# ProPrj_ExtModule-003_2025-06-06.net
KiCad netlist of a schematic drawn in EasyEDA Pro
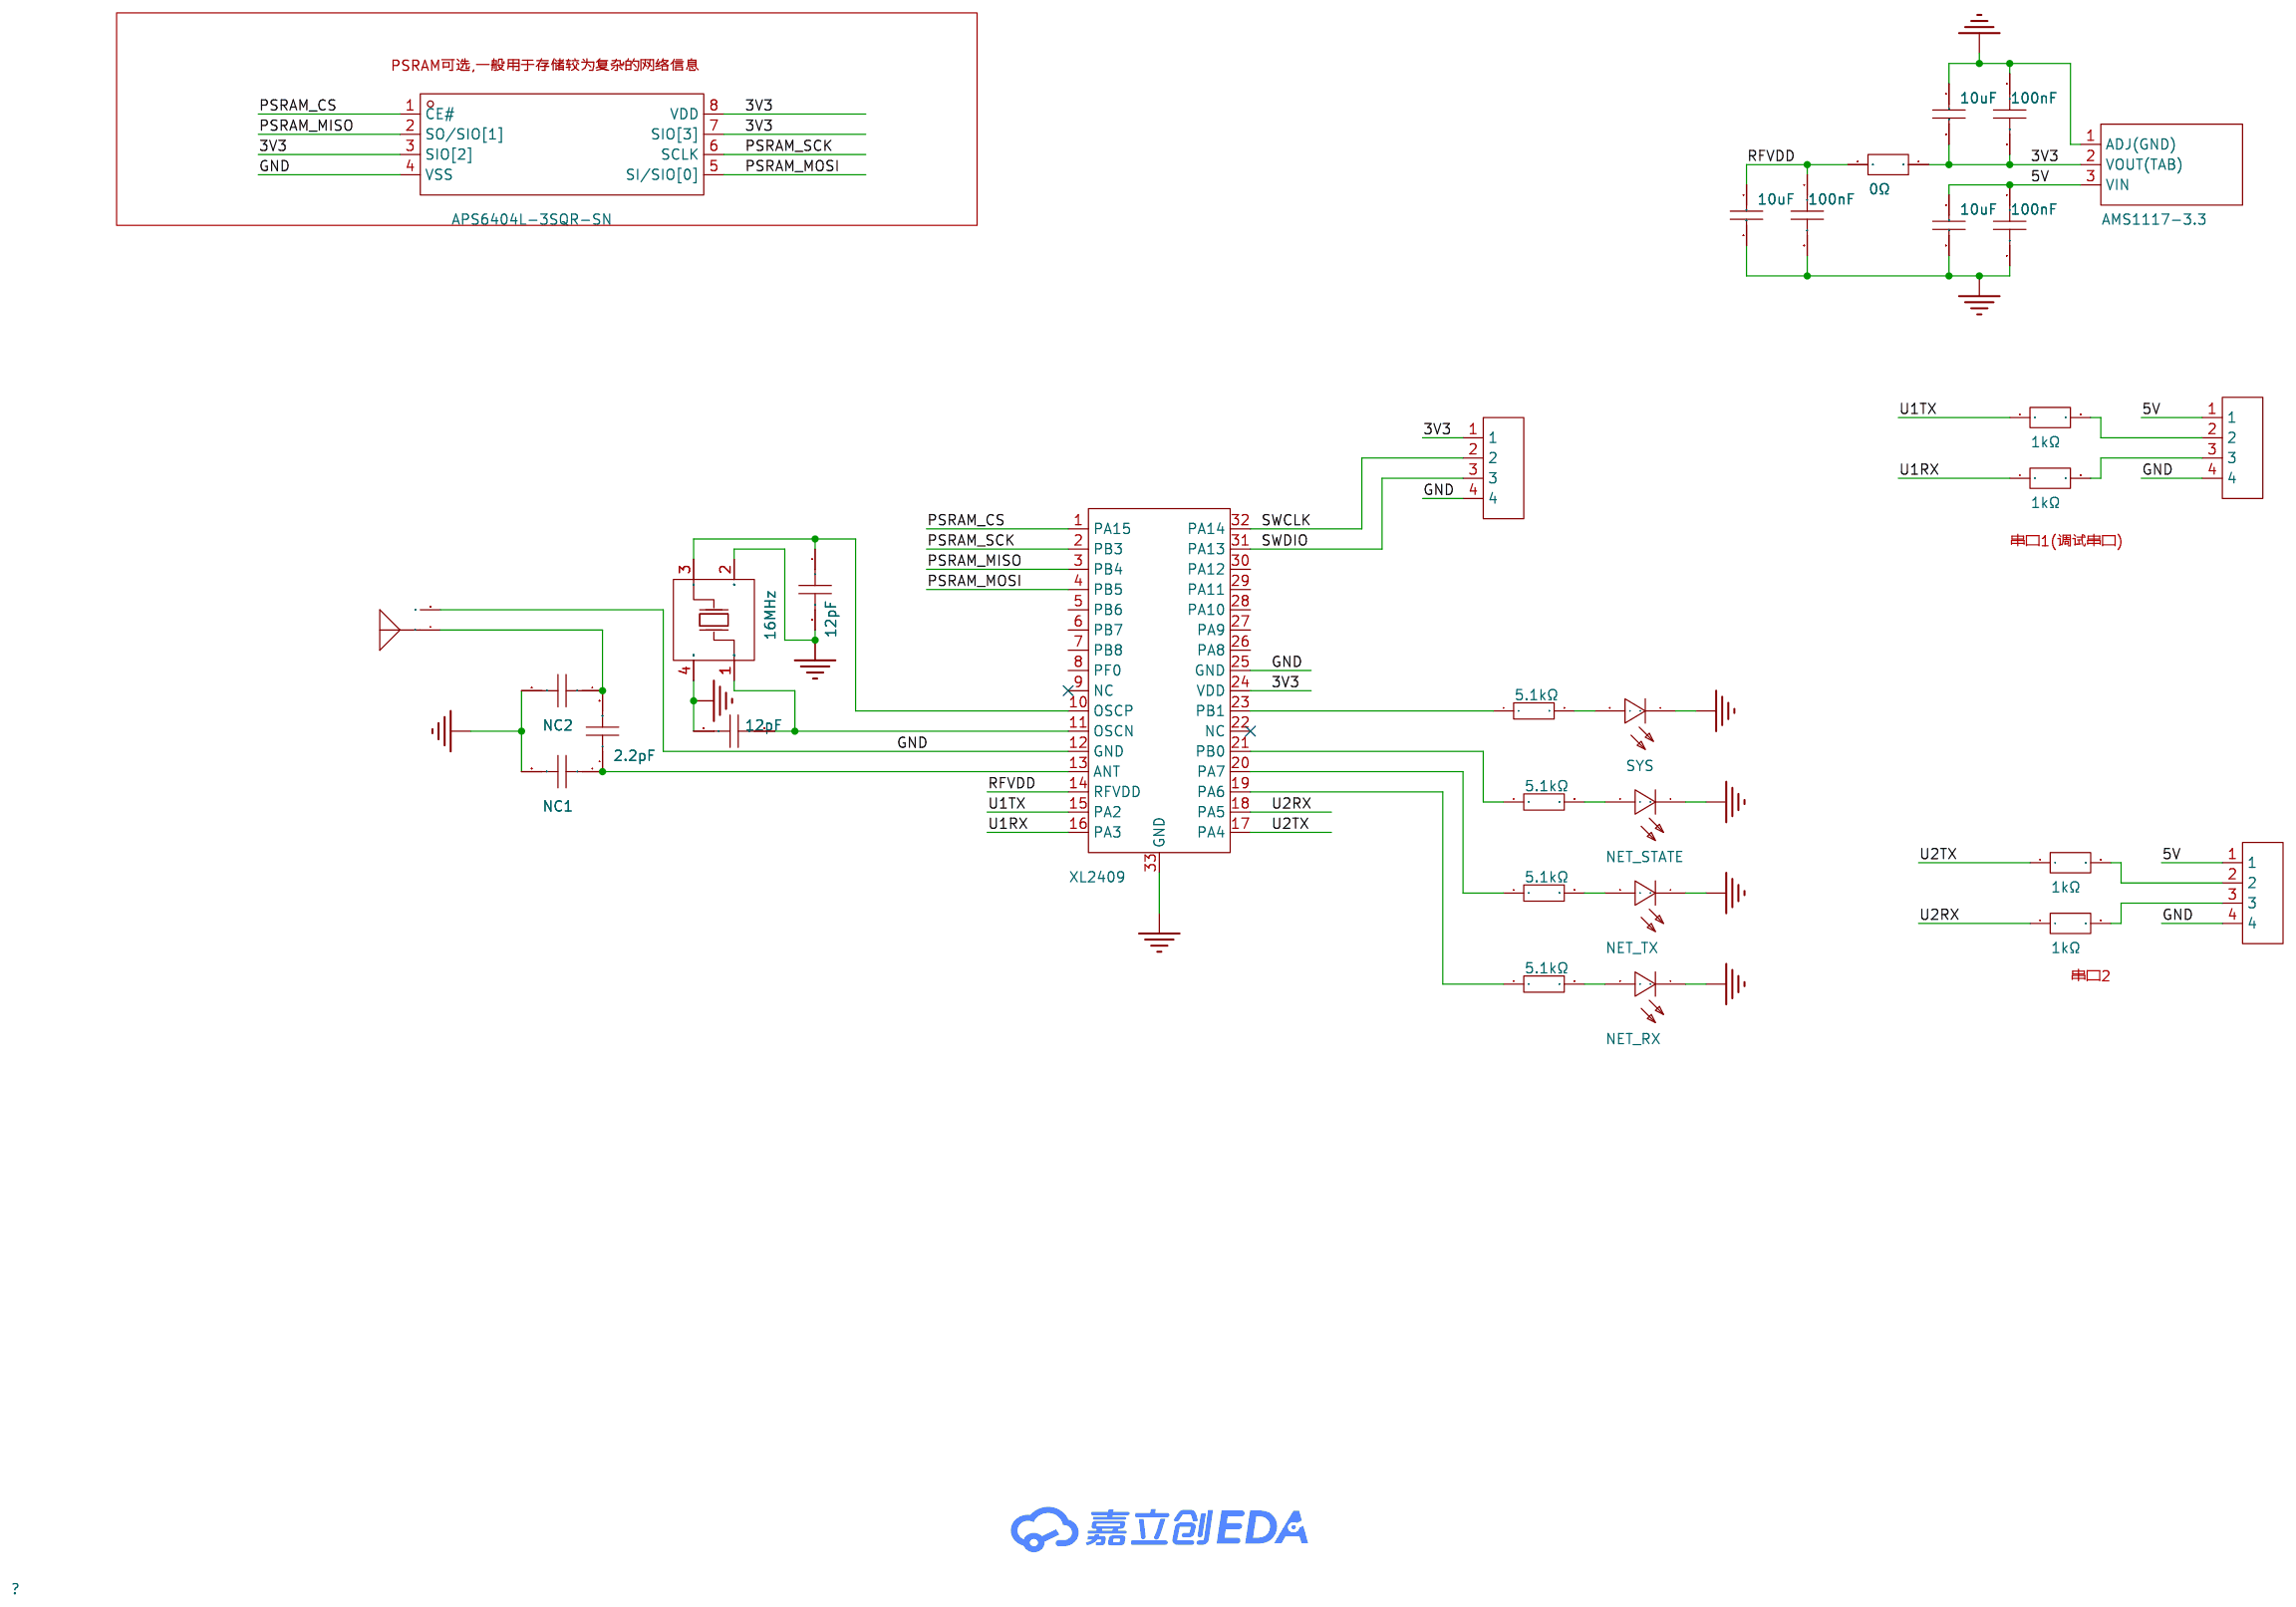
[diagram p0: schematic sheet]

(export (version "E")
  (design (tool "Eeschema 10.0.6"))
  (components
    (comp (ref "C3")
      (value "100nF")
      (footprint "easyedapro:C0402")
      (description "容值:100nF;精度:±10%;额定电压:16V;材质(温度系数):X7R;")
      (fields
        (field (name "Manufacturer Part") "CC0402KRX7R7BB104")
        (field (name "Manufacturer") "YAGEO(国巨)")
      )
      (libsource (lib "easyedapro") (part "CC0402KRX7R7BB104"))
    )
    (comp (ref "C4")
      (value "10uF")
      (footprint "easyedapro:C0402")
      (description "容值:10uF;精度:±20%;额定电压:6.3V;材质(温度系数):X5R;")
      (fields
        (field (name "Manufacturer Part") "CL05A106MQ5NUNC")
        (field (name "Manufacturer") "SAMSUNG(三星)")
      )
      (libsource (lib "easyedapro") (part "CL05A106MQ5NUNC"))
    )
    (comp (ref "C5")
      (value "10uF")
      (footprint "easyedapro:C0402")
      (description "容值:10uF;精度:±20%;额定电压:6.3V;材质(温度系数):X5R;")
      (fields
        (field (name "Manufacturer Part") "CL05A106MQ5NUNC")
        (field (name "Manufacturer") "SAMSUNG(三星)")
      )
      (libsource (lib "easyedapro") (part "CL05A106MQ5NUNC"))
    )
    (comp (ref "C6")
      (value "100nF")
      (footprint "easyedapro:C0402")
      (description "容值:100nF;精度:±10%;额定电压:16V;材质(温度系数):X7R;")
      (fields
        (field (name "Manufacturer Part") "CC0402KRX7R7BB104")
        (field (name "Manufacturer") "YAGEO(国巨)")
      )
      (libsource (lib "easyedapro") (part "CC0402KRX7R7BB104"))
    )
    (comp (ref "C7")
      (value "10uF")
      (footprint "easyedapro:C0402")
      (description "容值:10uF;精度:±20%;额定电压:6.3V;材质(温度系数):X5R;")
      (fields
        (field (name "Manufacturer Part") "CL05A106MQ5NUNC")
        (field (name "Manufacturer") "SAMSUNG(三星)")
      )
      (libsource (lib "easyedapro") (part "CL05A106MQ5NUNC"))
    )
    (comp (ref "C8")
      (value "100nF")
      (footprint "easyedapro:C0402")
      (description "容值:100nF;精度:±10%;额定电压:16V;材质(温度系数):X7R;")
      (fields
        (field (name "Manufacturer Part") "CC0402KRX7R7BB104")
        (field (name "Manufacturer") "YAGEO(国巨)")
      )
      (libsource (lib "easyedapro") (part "CC0402KRX7R7BB104"))
    )
    (comp (ref "C9")
      (value "2.2pF")
      (footprint "easyedapro:C0402")
      (description "容值:2.2pF;额定电压:50V;材质(温度系数):NP0;")
      (fields
        (field (name "Manufacturer Part") "CC0402BRNPO9BN2R2")
        (field (name "Manufacturer") "YAGEO(国巨)")
      )
      (libsource (lib "easyedapro") (part "CC0402BRNPO9BN2R2"))
    )
    (comp (ref "C10")
      (value "12pF")
      (footprint "easyedapro:C0402")
      (description "容值:12pF;精度:±1%;额定电压:50V;材质(温度系数):NP0;")
      (fields
        (field (name "Manufacturer Part") "CC0402FRNPO9BN120")
        (field (name "Manufacturer") "YAGEO(国巨)")
      )
      (libsource (lib "easyedapro") (part "CC0402FRNPO9BN120"))
    )
    (comp (ref "C11")
      (value "12pF")
      (footprint "easyedapro:C0402")
      (description "容值:12pF;精度:±1%;额定电压:50V;材质(温度系数):NP0;")
      (fields
        (field (name "Manufacturer Part") "CC0402FRNPO9BN120")
        (field (name "Manufacturer") "YAGEO(国巨)")
      )
      (libsource (lib "easyedapro") (part "CC0402FRNPO9BN120"))
    )
    (comp (ref "H1")
      (value "PZ254R-11-04P")
      (footprint "easyedapro:HDR-TH_4P-P2.54-H-M-W10.4")
      (fields (field (name "Manufacturer") "XFCN(兴飞)"))
      (libsource (lib "easyedapro") (part "PZ254R-11-04P"))
    )
    (comp (ref "H2")
      (value "PZ254R-11-04P")
      (footprint "easyedapro:HDR-TH_4P-P2.54-H-M-W10.4")
      (fields (field (name "Manufacturer") "XFCN(兴飞)"))
      (libsource (lib "easyedapro") (part "PZ254R-11-04P"))
    )
    (comp (ref "H3")
      (value "PZ254R-11-04P")
      (footprint "easyedapro:HDR-TH_4P-P2.54-H-M-W10.4")
      (fields (field (name "Manufacturer") "XFCN(兴飞)"))
      (libsource (lib "easyedapro") (part "PZ254R-11-04P"))
    )
    (comp (ref "L1")
      (value "KH-3216-A27")
      (footprint "easyedapro:ANT-SMD_L3.2-W1.6")
      (fields (field (name "Manufacturer") "kinghelm(金航标)"))
      (libsource (lib "easyedapro") (part "KH-3216-A27"))
    )
    (comp (ref "LED2")
      (value "SYS")
      (footprint "easyedapro:LED0603-RD_RED")
      (fields (field (name "Manufacturer Part") "NCD0603R1") (field (name "Manufacturer") "国星光电"))
      (libsource (lib "easyedapro") (part "FC-DA1608HRK-620D"))
    )
    (comp (ref "LED3")
      (value "NET_STATE")
      (footprint "easyedapro:LED0603-RD_RED")
      (fields (field (name "Manufacturer Part") "NCD0603R1") (field (name "Manufacturer") "国星光电"))
      (libsource (lib "easyedapro") (part "FC-DA1608HRK-620D"))
    )
    (comp (ref "LED4")
      (value "NET_TX")
      (footprint "easyedapro:LED0603-RD_RED")
      (fields (field (name "Manufacturer Part") "NCD0603R1") (field (name "Manufacturer") "国星光电"))
      (libsource (lib "easyedapro") (part "FC-DA1608HRK-620D"))
    )
    (comp (ref "LED5")
      (value "NET_RX")
      (footprint "easyedapro:LED0603-RD_RED")
      (fields (field (name "Manufacturer Part") "NCD0603R1") (field (name "Manufacturer") "国星光电"))
      (libsource (lib "easyedapro") (part "FC-DA1608HRK-620D"))
    )
    (comp (ref "NC1")
      (value "9pF")
      (footprint "easyedapro:C0402")
      (description "容值:9pF;额定电压:50V;材质(温度系数):NP0;")
      (fields
        (field (name "Manufacturer Part") "CC0402CRNPO9BN9R0")
        (field (name "Manufacturer") "YAGEO(国巨)")
      )
      (libsource (lib "easyedapro") (part "CC0402CRNPO9BN9R0"))
    )
    (comp (ref "NC2")
      (value "9pF")
      (footprint "easyedapro:C0402")
      (description "容值:9pF;额定电压:50V;材质(温度系数):NP0;")
      (fields
        (field (name "Manufacturer Part") "CC0402CRNPO9BN9R0")
        (field (name "Manufacturer") "YAGEO(国巨)")
      )
      (libsource (lib "easyedapro") (part "CC0402CRNPO9BN9R0"))
    )
    (comp (ref "R1")
      (value "0Ω")
      (footprint "easyedapro:R0402")
      (description "电阻类型:厚膜电阻;阻值:0Ω;精度:±5%;功率:62.5mW;最大工作电压:50V;")
      (fields (field (name "Manufacturer Part") "FRC0402P000 TS") (field (name "Manufacturer") "FOJAN(富捷)"))
      (libsource (lib "easyedapro") (part "FRC0402P000 TS"))
    )
    (comp (ref "R18")
      (value "5.1kΩ")
      (footprint "easyedapro:R0402")
      (description "阻值:5.1kΩ;精度:±1%;功率:62.5mW;温度系数:±100ppm/°C;电阻类型:厚膜电阻;")
      (fields
        (field (name "Manufacturer Part") "0402WGF5101TCE")
        (field (name "Manufacturer") "UNI-ROYAL(厚声)")
      )
      (libsource (lib "easyedapro") (part "0402WGF5101TCE"))
    )
    (comp (ref "R19")
      (value "5.1kΩ")
      (footprint "easyedapro:R0402")
      (description "阻值:5.1kΩ;精度:±1%;功率:62.5mW;温度系数:±100ppm/°C;电阻类型:厚膜电阻;")
      (fields
        (field (name "Manufacturer Part") "0402WGF5101TCE")
        (field (name "Manufacturer") "UNI-ROYAL(厚声)")
      )
      (libsource (lib "easyedapro") (part "0402WGF5101TCE"))
    )
    (comp (ref "R20")
      (value "5.1kΩ")
      (footprint "easyedapro:R0402")
      (description "阻值:5.1kΩ;精度:±1%;功率:62.5mW;温度系数:±100ppm/°C;电阻类型:厚膜电阻;")
      (fields
        (field (name "Manufacturer Part") "0402WGF5101TCE")
        (field (name "Manufacturer") "UNI-ROYAL(厚声)")
      )
      (libsource (lib "easyedapro") (part "0402WGF5101TCE"))
    )
    (comp (ref "R21")
      (value "5.1kΩ")
      (footprint "easyedapro:R0402")
      (description "阻值:5.1kΩ;精度:±1%;功率:62.5mW;温度系数:±100ppm/°C;电阻类型:厚膜电阻;")
      (fields
        (field (name "Manufacturer Part") "0402WGF5101TCE")
        (field (name "Manufacturer") "UNI-ROYAL(厚声)")
      )
      (libsource (lib "easyedapro") (part "0402WGF5101TCE"))
    )
    (comp (ref "R22")
      (value "1kΩ")
      (footprint "easyedapro:R0402")
      (description "电阻类型:薄膜电阻;阻值:1kΩ;精度:±0.1%;功率:62.5mW;最大工作电压:50V;温度系数:±25ppm/°C;")
      (fields (field (name "Manufacturer Part") "RT0402BRD071KL") (field (name "Manufacturer") "YAGEO(国巨)"))
      (libsource (lib "easyedapro") (part "RT0402BRD071KL"))
    )
    (comp (ref "R23")
      (value "1kΩ")
      (footprint "easyedapro:R0402")
      (description "电阻类型:薄膜电阻;阻值:1kΩ;精度:±0.1%;功率:62.5mW;最大工作电压:50V;温度系数:±25ppm/°C;")
      (fields (field (name "Manufacturer Part") "RT0402BRD071KL") (field (name "Manufacturer") "YAGEO(国巨)"))
      (libsource (lib "easyedapro") (part "RT0402BRD071KL"))
    )
    (comp (ref "R24")
      (value "1kΩ")
      (footprint "easyedapro:R0402")
      (description "电阻类型:薄膜电阻;阻值:1kΩ;精度:±0.1%;功率:62.5mW;最大工作电压:50V;温度系数:±25ppm/°C;")
      (fields (field (name "Manufacturer Part") "RT0402BRD071KL") (field (name "Manufacturer") "YAGEO(国巨)"))
      (libsource (lib "easyedapro") (part "RT0402BRD071KL"))
    )
    (comp (ref "R25")
      (value "1kΩ")
      (footprint "easyedapro:R0402")
      (description "电阻类型:薄膜电阻;阻值:1kΩ;精度:±0.1%;功率:62.5mW;最大工作电压:50V;温度系数:±25ppm/°C;")
      (fields (field (name "Manufacturer Part") "RT0402BRD071KL") (field (name "Manufacturer") "YAGEO(国巨)"))
      (libsource (lib "easyedapro") (part "RT0402BRD071KL"))
    )
    (comp (ref "U1")
      (value "XL2409")
      (footprint "easyedapro:QFN-32_L4.0-W4.0-P0.40-BL-EP2.7-A")
      (libsource (lib "easyedapro") (part "XL2409"))
    )
    (comp (ref "U2")
      (value "AMS1117-3.3")
      (footprint "easyedapro:SOT-89_L4.5-W2.5-P1.50-LS4.2-BR")
      (description "输出类型:固定;工作电压:18V;输出电压:3.3V;输出电流:1A;电源纹波抑制比(PSRR):60dB@(120Hz);输出极性:正极;")
      (fields (field (name "Manufacturer") "UMW(友台半导体)"))
      (libsource (lib "easyedapro") (part "AMS1117-3.3_C347256"))
    )
    (comp (ref "U3")
      (value "APS6404L-3SQR-SN")
      (footprint "easyedapro:SOIC-8_L4.9-W3.9-P1.27-LS6.0-BL")
      (fields (field (name "Manufacturer") "Apmemory"))
      (libsource (lib "easyedapro") (part "APS6404L-3SQR-SN_C5333729"))
    )
    (comp (ref "X1")
      (value "16MHz")
      (footprint "easyedapro:CRYSTAL-SMD_4P-L3.2-W2.5-BL")
      (description "晶振类型:贴片晶振;频率:16MHz;常温频差:±10ppm;负载电容:12pF;频率稳定度:±20ppm;")
      (fields (field (name "Manufacturer Part") "X322516MOB4SI") (field (name "Manufacturer") "YXC(扬兴晶振)"))
      (libsource (lib "easyedapro") (part "X322516MOB4SI"))
    )
  )
  (nets
    (net (code "1") (name "/3V3") (class "Default")
      (node (ref "C3") (pin "2") (pinfunction "2_2") (pintype "unspecified"))
      (node (ref "C4") (pin "2") (pinfunction "2_2") (pintype "input"))
      (node (ref "H1") (pin "1") (pinfunction "1_1") (pintype "unspecified"))
      (node (ref "R1") (pin "1") (pinfunction "1_1") (pintype "unspecified"))
      (node (ref "U1") (pin "24") (pinfunction "VDD_24") (pintype "unspecified"))
      (node (ref "U2") (pin "2") (pinfunction "VOUT(TAB)_2") (pintype "unspecified"))
      (node (ref "U3") (pin "3") (pinfunction "SIO[2]_3") (pintype "unspecified"))
      (node (ref "U3") (pin "7") (pinfunction "SIO[3]_7") (pintype "unspecified"))
      (node (ref "U3") (pin "8") (pinfunction "VDD_8") (pintype "unspecified"))
    )
    (net (code "2") (name "/5V") (class "Default")
      (node (ref "C5") (pin "1") (pinfunction "1_1") (pintype "input"))
      (node (ref "C6") (pin "1") (pinfunction "1_1") (pintype "unspecified"))
      (node (ref "H2") (pin "1") (pinfunction "1_1") (pintype "unspecified"))
      (node (ref "H3") (pin "1") (pinfunction "1_1") (pintype "unspecified"))
      (node (ref "U2") (pin "3") (pinfunction "VIN_3") (pintype "unspecified"))
    )
    (net (code "3") (name "/PSRAM_CS") (class "Default")
      (node (ref "U1") (pin "1") (pinfunction "PA15_1") (pintype "unspecified"))
      (node (ref "U3") (pin "1") (pinfunction "CE#_1") (pintype "unspecified"))
    )
    (net (code "4") (name "/PSRAM_MISO") (class "Default")
      (node (ref "U1") (pin "3") (pinfunction "PB4_3") (pintype "unspecified"))
      (node (ref "U3") (pin "2") (pinfunction "SO/SIO[1]_2") (pintype "unspecified"))
    )
    (net (code "5") (name "/PSRAM_MOSI") (class "Default")
      (node (ref "U1") (pin "4") (pinfunction "PB5_4") (pintype "unspecified"))
      (node (ref "U3") (pin "5") (pinfunction "SI/SIO[0]_5") (pintype "unspecified"))
    )
    (net (code "6") (name "/PSRAM_SCK") (class "Default")
      (node (ref "U1") (pin "2") (pinfunction "PB3_2") (pintype "unspecified"))
      (node (ref "U3") (pin "6") (pinfunction "SCLK_6") (pintype "unspecified"))
    )
    (net (code "7") (name "/RFVDD") (class "Default")
      (node (ref "C7") (pin "1") (pinfunction "1_1") (pintype "input"))
      (node (ref "C8") (pin "1") (pinfunction "1_1") (pintype "unspecified"))
      (node (ref "R1") (pin "2") (pinfunction "2_2") (pintype "unspecified"))
      (node (ref "U1") (pin "14") (pinfunction "RFVDD_14") (pintype "unspecified"))
    )
    (net (code "8") (name "/SWCLK") (class "Default")
      (node (ref "H1") (pin "2") (pinfunction "2_2") (pintype "unspecified"))
      (node (ref "U1") (pin "32") (pinfunction "PA14_32") (pintype "unspecified"))
    )
    (net (code "9") (name "/SWDIO") (class "Default")
      (node (ref "H1") (pin "3") (pinfunction "3_3") (pintype "unspecified"))
      (node (ref "U1") (pin "31") (pinfunction "PA13_31") (pintype "unspecified"))
    )
    (net (code "10") (name "/U1RX") (class "Default")
      (node (ref "R23") (pin "1") (pinfunction "1_1") (pintype "unspecified"))
      (node (ref "U1") (pin "16") (pinfunction "PA3_16") (pintype "unspecified"))
    )
    (net (code "11") (name "/U1TX") (class "Default")
      (node (ref "R22") (pin "1") (pinfunction "1_1") (pintype "unspecified"))
      (node (ref "U1") (pin "15") (pinfunction "PA2_15") (pintype "unspecified"))
    )
    (net (code "12") (name "/U2RX") (class "Default")
      (node (ref "R25") (pin "1") (pinfunction "1_1") (pintype "unspecified"))
      (node (ref "U1") (pin "18") (pinfunction "PA5_18") (pintype "unspecified"))
    )
    (net (code "13") (name "/U2TX") (class "Default")
      (node (ref "R24") (pin "1") (pinfunction "1_1") (pintype "unspecified"))
      (node (ref "U1") (pin "17") (pinfunction "PA4_17") (pintype "unspecified"))
    )
    (net (code "14") (name "GND") (class "Default")
      (node (ref "C10") (pin "2") (pinfunction "2_2") (pintype "unspecified"))
      (node (ref "C11") (pin "2") (pinfunction "2_2") (pintype "unspecified"))
      (node (ref "C3") (pin "1") (pinfunction "1_1") (pintype "unspecified"))
      (node (ref "C4") (pin "1") (pinfunction "1_1") (pintype "input"))
      (node (ref "C5") (pin "2") (pinfunction "2_2") (pintype "input"))
      (node (ref "C6") (pin "2") (pinfunction "2_2") (pintype "unspecified"))
      (node (ref "C7") (pin "2") (pinfunction "2_2") (pintype "input"))
      (node (ref "C8") (pin "2") (pinfunction "2_2") (pintype "unspecified"))
      (node (ref "H1") (pin "4") (pinfunction "4_4") (pintype "unspecified"))
      (node (ref "H2") (pin "4") (pinfunction "4_4") (pintype "unspecified"))
      (node (ref "H3") (pin "4") (pinfunction "4_4") (pintype "unspecified"))
      (node (ref "L1") (pin "2") (pinfunction "2_2") (pintype "unspecified"))
      (node (ref "LED2") (pin "1") (pinfunction "K_1") (pintype "input"))
      (node (ref "LED3") (pin "1") (pinfunction "K_1") (pintype "input"))
      (node (ref "LED4") (pin "1") (pinfunction "K_1") (pintype "input"))
      (node (ref "LED5") (pin "1") (pinfunction "K_1") (pintype "input"))
      (node (ref "NC1") (pin "2") (pinfunction "2_2") (pintype "unspecified"))
      (node (ref "NC2") (pin "2") (pinfunction "2_2") (pintype "unspecified"))
      (node (ref "U1") (pin "12") (pinfunction "GND_12") (pintype "unspecified"))
      (node (ref "U1") (pin "25") (pinfunction "GND_25") (pintype "unspecified"))
      (node (ref "U1") (pin "33") (pinfunction "GND_33") (pintype "unspecified"))
      (node (ref "U2") (pin "1") (pinfunction "ADJ(GND)_1") (pintype "unspecified"))
      (node (ref "U3") (pin "4") (pinfunction "VSS_4") (pintype "unspecified"))
      (node (ref "X1") (pin "2") (pinfunction "GND_2") (pintype "unspecified"))
      (node (ref "X1") (pin "4") (pinfunction "GND_4") (pintype "unspecified"))
    )
    (net (code "15") (name "Net-(H2-Pad2)") (class "Default")
      (node (ref "H2") (pin "2") (pinfunction "2_2") (pintype "unspecified"))
      (node (ref "R22") (pin "2") (pinfunction "2_2") (pintype "unspecified"))
    )
    (net (code "16") (name "Net-(H2-Pad3)") (class "Default")
      (node (ref "H2") (pin "3") (pinfunction "3_3") (pintype "unspecified"))
      (node (ref "R23") (pin "2") (pinfunction "2_2") (pintype "unspecified"))
    )
    (net (code "17") (name "Net-(H3-Pad2)") (class "Default")
      (node (ref "H3") (pin "2") (pinfunction "2_2") (pintype "unspecified"))
      (node (ref "R24") (pin "2") (pinfunction "2_2") (pintype "unspecified"))
    )
    (net (code "18") (name "Net-(H3-Pad3)") (class "Default")
      (node (ref "H3") (pin "3") (pinfunction "3_3") (pintype "unspecified"))
      (node (ref "R25") (pin "2") (pinfunction "2_2") (pintype "unspecified"))
    )
    (net (code "19") (name "Net-(L1-ANT)") (class "Default")
      (node (ref "C9") (pin "2") (pinfunction "2_2") (pintype "unspecified"))
      (node (ref "L1") (pin "1") (pinfunction "ANT_1") (pintype "unspecified"))
      (node (ref "NC2") (pin "1") (pinfunction "1_1") (pintype "unspecified"))
    )
    (net (code "20") (name "Net-(LED2-A)") (class "Default")
      (node (ref "LED2") (pin "2") (pinfunction "A_2") (pintype "input"))
      (node (ref "R18") (pin "2") (pinfunction "2_2") (pintype "input"))
    )
    (net (code "21") (name "Net-(LED3-A)") (class "Default")
      (node (ref "LED3") (pin "2") (pinfunction "A_2") (pintype "input"))
      (node (ref "R19") (pin "2") (pinfunction "2_2") (pintype "input"))
    )
    (net (code "22") (name "Net-(LED4-A)") (class "Default")
      (node (ref "LED4") (pin "2") (pinfunction "A_2") (pintype "input"))
      (node (ref "R20") (pin "2") (pinfunction "2_2") (pintype "input"))
    )
    (net (code "23") (name "Net-(LED5-A)") (class "Default")
      (node (ref "LED5") (pin "2") (pinfunction "A_2") (pintype "input"))
      (node (ref "R21") (pin "2") (pinfunction "2_2") (pintype "input"))
    )
    (net (code "24") (name "Net-(U1-ANT)") (class "Default")
      (node (ref "C9") (pin "1") (pinfunction "1_1") (pintype "unspecified"))
      (node (ref "NC1") (pin "1") (pinfunction "1_1") (pintype "unspecified"))
      (node (ref "U1") (pin "13") (pinfunction "ANT_13") (pintype "unspecified"))
    )
    (net (code "25") (name "Net-(U1-OSCN)") (class "Default")
      (node (ref "C10") (pin "1") (pinfunction "1_1") (pintype "unspecified"))
      (node (ref "U1") (pin "11") (pinfunction "OSCN_11") (pintype "unspecified"))
      (node (ref "X1") (pin "1") (pinfunction "OSC1_1") (pintype "unspecified"))
    )
    (net (code "26") (name "Net-(U1-OSCP)") (class "Default")
      (node (ref "C11") (pin "1") (pinfunction "1_1") (pintype "unspecified"))
      (node (ref "U1") (pin "10") (pinfunction "OSCP_10") (pintype "unspecified"))
      (node (ref "X1") (pin "3") (pinfunction "OSC2_3") (pintype "unspecified"))
    )
    (net (code "27") (name "Net-(U1-PA6)") (class "Default")
      (node (ref "R21") (pin "1") (pinfunction "1_1") (pintype "input"))
      (node (ref "U1") (pin "19") (pinfunction "PA6_19") (pintype "unspecified"))
    )
    (net (code "28") (name "Net-(U1-PA7)") (class "Default")
      (node (ref "R20") (pin "1") (pinfunction "1_1") (pintype "input"))
      (node (ref "U1") (pin "20") (pinfunction "PA7_20") (pintype "unspecified"))
    )
    (net (code "29") (name "Net-(U1-PB0)") (class "Default")
      (node (ref "R19") (pin "1") (pinfunction "1_1") (pintype "input"))
      (node (ref "U1") (pin "21") (pinfunction "PB0_21") (pintype "unspecified"))
    )
    (net (code "30") (name "Net-(U1-PB1)") (class "Default")
      (node (ref "R18") (pin "1") (pinfunction "1_1") (pintype "input"))
      (node (ref "U1") (pin "23") (pinfunction "PB1_23") (pintype "unspecified"))
    )
    (net (code "31") (name "unconnected-(U1-NC-Pad9)") (class "Default")
      (node (ref "U1") (pin "9") (pinfunction "NC_9") (pintype "unspecified+no_connect"))
    )
    (net (code "32") (name "unconnected-(U1-NC-Pad22)") (class "Default")
      (node (ref "U1") (pin "22") (pinfunction "NC_22") (pintype "unspecified+no_connect"))
    )
    (net (code "33") (name "unconnected-(U1-PA8-Pad26)") (class "Default")
      (node (ref "U1") (pin "26") (pinfunction "PA8_26") (pintype "unspecified"))
    )
    (net (code "34") (name "unconnected-(U1-PA9-Pad27)") (class "Default")
      (node (ref "U1") (pin "27") (pinfunction "PA9_27") (pintype "unspecified"))
    )
    (net (code "35") (name "unconnected-(U1-PA10-Pad28)") (class "Default")
      (node (ref "U1") (pin "28") (pinfunction "PA10_28") (pintype "unspecified"))
    )
    (net (code "36") (name "unconnected-(U1-PA11-Pad29)") (class "Default")
      (node (ref "U1") (pin "29") (pinfunction "PA11_29") (pintype "unspecified"))
    )
    (net (code "37") (name "unconnected-(U1-PA12-Pad30)") (class "Default")
      (node (ref "U1") (pin "30") (pinfunction "PA12_30") (pintype "unspecified"))
    )
    (net (code "38") (name "unconnected-(U1-PB6-Pad5)") (class "Default")
      (node (ref "U1") (pin "5") (pinfunction "PB6_5") (pintype "unspecified"))
    )
    (net (code "39") (name "unconnected-(U1-PB7-Pad6)") (class "Default")
      (node (ref "U1") (pin "6") (pinfunction "PB7_6") (pintype "unspecified"))
    )
    (net (code "40") (name "unconnected-(U1-PB8-Pad7)") (class "Default")
      (node (ref "U1") (pin "7") (pinfunction "PB8_7") (pintype "unspecified"))
    )
    (net (code "41") (name "unconnected-(U1-PF0-Pad8)") (class "Default")
      (node (ref "U1") (pin "8") (pinfunction "PF0_8") (pintype "unspecified"))
    )
  )
)
